# esp_car.net
KiCad netlist of a schematic drawn in EAGLE
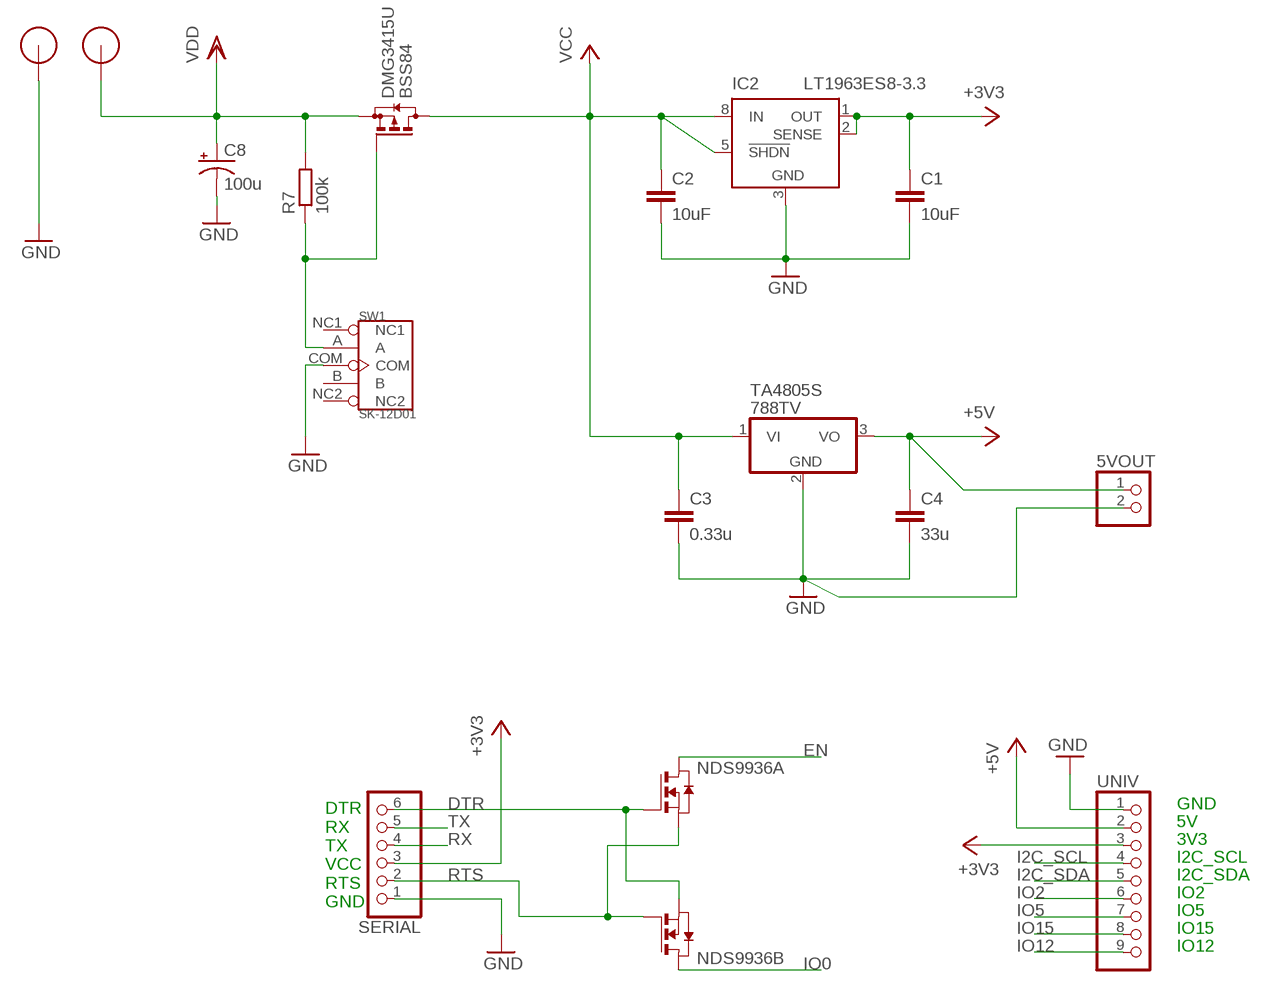
[diagram p0: schematic, sheet 1, part 1 of 2]
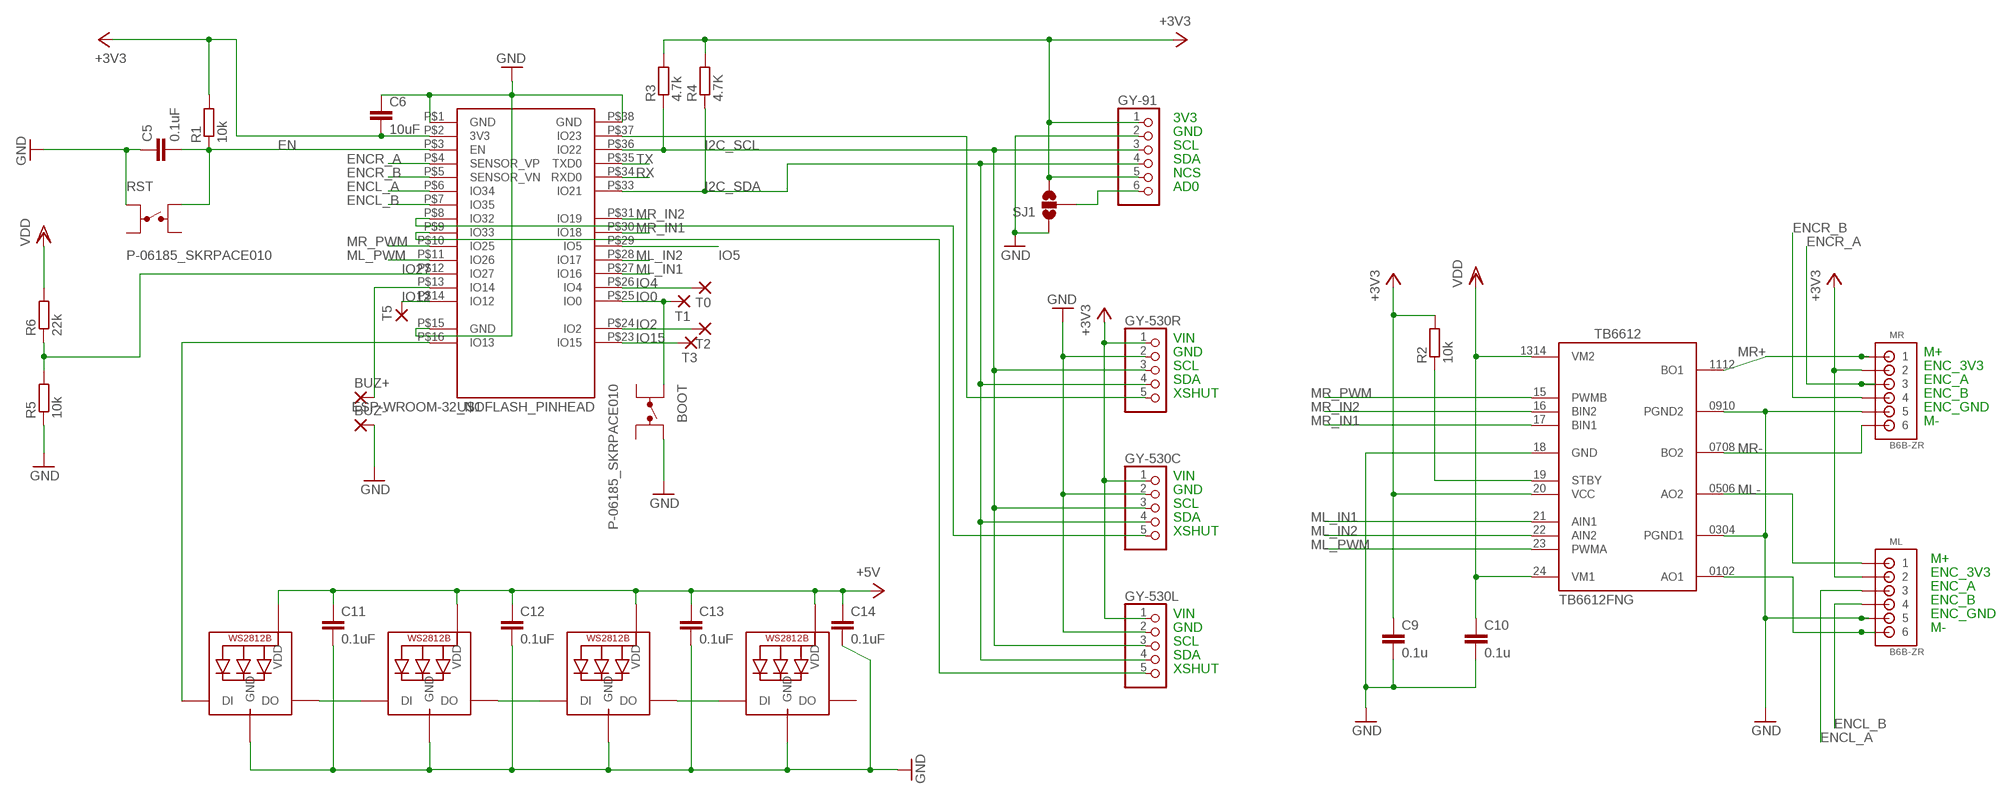
[diagram p1: schematic, sheet 1, part 2 of 2]

(export (version "E")
  (design (tool "Eeschema 10.0.6"))
  (components
    (comp (ref "5VOUT")
      (value "PINHD-1X2")
      (footprint "eagle-import:1X02")
      (libsource (lib "eagle-import") (part "PINHD-1X2"))
    )
    (comp (ref "BOOT")
      (value "P-06185_SKRPACE010")
      (footprint "eagle-import:SKRP")
      (libsource (lib "eagle-import") (part "P-06185_SKRPACE010"))
    )
    (comp (ref "BUZ+")
      (value "SMD2")
      (footprint "eagle-import:SMD1,27-2,54")
      (libsource (lib "eagle-import") (part "SMD2"))
    )
    (comp (ref "BUZ-")
      (value "SMD2")
      (footprint "eagle-import:SMD1,27-2,54")
      (libsource (lib "eagle-import") (part "SMD2"))
    )
    (comp (ref "C1")
      (value "10uF")
      (footprint "eagle-import:C1608")
      (libsource (lib "eagle-import") (part "C-EUC1608"))
    )
    (comp (ref "C2")
      (value "10uF")
      (footprint "eagle-import:C1608")
      (libsource (lib "eagle-import") (part "C-EUC1608"))
    )
    (comp (ref "C3")
      (value "0.33u")
      (footprint "eagle-import:C1608")
      (libsource (lib "eagle-import") (part "C-EUC1608"))
    )
    (comp (ref "C4")
      (value "33u")
      (footprint "eagle-import:C3225")
      (libsource (lib "eagle-import") (part "C-EUC3225"))
    )
    (comp (ref "C5")
      (value "0.1uF")
      (footprint "eagle-import:C1608")
      (libsource (lib "eagle-import") (part "C-EUC1608"))
    )
    (comp (ref "C6")
      (value "10uF")
      (footprint "eagle-import:C1608")
      (libsource (lib "eagle-import") (part "C-EUC1608"))
    )
    (comp (ref "C8")
      (value "100u")
      (footprint "eagle-import:E2,5-6")
      (libsource (lib "eagle-import") (part "CPOL-USE2.5-6"))
    )
    (comp (ref "C9")
      (value "0.1u")
      (footprint "eagle-import:C1608")
      (libsource (lib "eagle-import") (part "C-EUC1608"))
    )
    (comp (ref "C10")
      (value "0.1u")
      (footprint "eagle-import:C1608")
      (libsource (lib "eagle-import") (part "C-EUC1608"))
    )
    (comp (ref "C11")
      (value "0.1uF")
      (footprint "eagle-import:C1608")
      (libsource (lib "eagle-import") (part "C-EUC1608"))
    )
    (comp (ref "C12")
      (value "0.1uF")
      (footprint "eagle-import:C1608")
      (libsource (lib "eagle-import") (part "C-EUC1608"))
    )
    (comp (ref "C13")
      (value "0.1uF")
      (footprint "eagle-import:C1608")
      (libsource (lib "eagle-import") (part "C-EUC1608"))
    )
    (comp (ref "C14")
      (value "0.1uF")
      (footprint "eagle-import:C1608")
      (libsource (lib "eagle-import") (part "C-EUC1608"))
    )
    (comp (ref "DMG3415U")
      (value "BSS84")
      (footprint "eagle-import:SOT23")
      (libsource (lib "eagle-import") (part "BSS84"))
    )
    (comp (ref "GY-91")
      (value "PINHD-1X6")
      (footprint "eagle-import:1X06")
      (libsource (lib "eagle-import") (part "PINHD-1X6"))
    )
    (comp (ref "GY-530C")
      (value "PINHD-1X5")
      (footprint "eagle-import:1X05")
      (libsource (lib "eagle-import") (part "PINHD-1X5"))
    )
    (comp (ref "GY-530L")
      (value "PINHD-1X5")
      (footprint "eagle-import:1X05")
      (libsource (lib "eagle-import") (part "PINHD-1X5"))
    )
    (comp (ref "GY-530R")
      (value "PINHD-1X5")
      (footprint "eagle-import:1X05")
      (libsource (lib "eagle-import") (part "PINHD-1X5"))
    )
    (comp (ref "IC2")
      (value "LT1963ES8-3.3")
      (footprint "eagle-import:SOIC8")
      (libsource (lib "eagle-import") (part "LT1963ES8-3.3"))
    )
    (comp (ref "LED_FL")
      (value "WS2812B5050")
      (footprint "eagle-import:WS2812B")
      (libsource (lib "eagle-import") (part "WS2812B5050"))
    )
    (comp (ref "LED_FR")
      (value "WS2812B5050")
      (footprint "eagle-import:WS2812B")
      (libsource (lib "eagle-import") (part "WS2812B5050"))
    )
    (comp (ref "LED_RL")
      (value "WS2812B5050")
      (footprint "eagle-import:WS2812B")
      (libsource (lib "eagle-import") (part "WS2812B5050"))
    )
    (comp (ref "LED_RR")
      (value "WS2812B5050")
      (footprint "eagle-import:WS2812B")
      (libsource (lib "eagle-import") (part "WS2812B5050"))
    )
    (comp (ref "ML")
      (value "B6B-ZR")
      (footprint "eagle-import:B6B-ZR")
      (libsource (lib "eagle-import") (part "B6B-ZR"))
    )
    (comp (ref "MR")
      (value "B6B-ZR")
      (footprint "eagle-import:B6B-ZR")
      (libsource (lib "eagle-import") (part "B6B-ZR"))
    )
    (comp (ref "NDS9936")
      (value "NMOS2SO8")
      (footprint "eagle-import:SO8")
      (libsource (lib "eagle-import") (part "NMOS2SO8"))
    )
    (comp (ref "R1")
      (value "10k")
      (footprint "eagle-import:R0603")
      (libsource (lib "eagle-import") (part "R-EU_R0603"))
    )
    (comp (ref "R2")
      (value "10k")
      (footprint "eagle-import:R0603")
      (libsource (lib "eagle-import") (part "R-EU_R0603"))
    )
    (comp (ref "R3")
      (value "4.7k")
      (footprint "eagle-import:R0603")
      (libsource (lib "eagle-import") (part "R-EU_R0603"))
    )
    (comp (ref "R4")
      (value "4.7K")
      (footprint "eagle-import:R0603")
      (libsource (lib "eagle-import") (part "R-EU_R0603"))
    )
    (comp (ref "R5")
      (value "10k")
      (footprint "eagle-import:R0603")
      (libsource (lib "eagle-import") (part "R-EU_R0603"))
    )
    (comp (ref "R6")
      (value "22k")
      (footprint "eagle-import:R0603")
      (libsource (lib "eagle-import") (part "R-EU_R0603"))
    )
    (comp (ref "R7")
      (value "100k")
      (footprint "eagle-import:R0603")
      (libsource (lib "eagle-import") (part "R-EU_R0603"))
    )
    (comp (ref "RST")
      (value "P-06185_SKRPACE010")
      (footprint "eagle-import:SKRP")
      (libsource (lib "eagle-import") (part "P-06185_SKRPACE010"))
    )
    (comp (ref "SERIAL")
      (value "PINHD-1X6")
      (footprint "eagle-import:1X06")
      (libsource (lib "eagle-import") (part "PINHD-1X6"))
    )
    (comp (ref "SJ1")
      (value "SOLDERJUMPER_2WAYS")
      (footprint "eagle-import:SJ_3")
      (libsource (lib "eagle-import") (part "SOLDERJUMPER_2WAYS"))
    )
    (comp (ref "SW1")
      (value "SK-12D01")
      (footprint "eagle-import:SW5-2.0-8.8X4.4X4.7MM-90D")
      (libsource (lib "eagle-import") (part "DIP-TOGGLE-SWITCH-ON-ON(3+2P-8.8X4.6MM)"))
    )
    (comp (ref "T0")
      (value "SMD5")
      (footprint "eagle-import:SMD2,54-5,08")
      (libsource (lib "eagle-import") (part "SMD5"))
    )
    (comp (ref "T1")
      (value "SMD5")
      (footprint "eagle-import:SMD2,54-5,08")
      (libsource (lib "eagle-import") (part "SMD5"))
    )
    (comp (ref "T2")
      (value "SMD5")
      (footprint "eagle-import:SMD2,54-5,08")
      (libsource (lib "eagle-import") (part "SMD5"))
    )
    (comp (ref "T3")
      (value "SMD5")
      (footprint "eagle-import:SMD2,54-5,08")
      (libsource (lib "eagle-import") (part "SMD5"))
    )
    (comp (ref "T5")
      (value "SMD5")
      (footprint "eagle-import:SMD2,54-5,08")
      (libsource (lib "eagle-import") (part "SMD5"))
    )
    (comp (ref "TA4805S")
      (value "788TV")
      (footprint "eagle-import:TO220V")
      (libsource (lib "eagle-import") (part "78TV8"))
    )
    (comp (ref "TB6612")
      (value "TB6612_NEW")
      (footprint "eagle-import:SSOP24_TB6612")
      (libsource (lib "eagle-import") (part "TB6612_NEW"))
    )
    (comp (ref "U$1")
      (value "ESP-WROOM-32_NOFLASH_PINHEAD")
      (footprint "eagle-import:ESP-WROOM-32_NOFLASH_PINHEAD")
      (libsource (lib "eagle-import") (part "ESP-WROOM-32_NOFLASH_PINHEAD"))
    )
    (comp (ref "U$5")
      (value "2.0")
      (footprint "eagle-import:2.0")
      (libsource (lib "eagle-import") (part "2.0"))
    )
    (comp (ref "U$7")
      (value "2.0")
      (footprint "eagle-import:2.0")
      (libsource (lib "eagle-import") (part "2.0"))
    )
    (comp (ref "UNIV")
      (value "PINHD-1X9")
      (footprint "eagle-import:1X09-BIG")
      (libsource (lib "eagle-import") (part "PINHD-1X9"))
    )
  )
  (nets
    (net (code "1") (name "+3V3") (class "Default")
      (node (ref "C1") (pin "1") (pinfunction "1_1") (pintype "passive"))
      (node (ref "C6") (pin "2") (pinfunction "2_2") (pintype "passive"))
      (node (ref "C9") (pin "1") (pinfunction "1_1") (pintype "passive"))
      (node (ref "GY-530C") (pin "1") (pinfunction "1_1") (pintype "passive"))
      (node (ref "GY-530L") (pin "1") (pinfunction "1_1") (pintype "passive"))
      (node (ref "GY-530R") (pin "1") (pinfunction "1_1") (pintype "passive"))
      (node (ref "GY-91") (pin "1") (pinfunction "1_1") (pintype "passive"))
      (node (ref "GY-91") (pin "5") (pinfunction "5_5") (pintype "passive"))
      (node (ref "IC2") (pin "1") (pinfunction "OUT_1") (pintype "output"))
      (node (ref "IC2") (pin "2") (pinfunction "SENSE_2") (pintype "input"))
      (node (ref "ML") (pin "2") (pinfunction "2_2") (pintype "bidirectional"))
      (node (ref "MR") (pin "2") (pinfunction "2_2") (pintype "bidirectional"))
      (node (ref "R1") (pin "2") (pinfunction "2_2") (pintype "passive"))
      (node (ref "R2") (pin "2") (pinfunction "2_2") (pintype "passive"))
      (node (ref "R3") (pin "2") (pinfunction "2_2") (pintype "passive"))
      (node (ref "R4") (pin "2") (pinfunction "2_2") (pintype "passive"))
      (node (ref "SERIAL") (pin "3") (pinfunction "3_3") (pintype "passive"))
      (node (ref "SJ1") (pin "3") (pinfunction "3_3") (pintype "passive"))
      (node (ref "TB6612") (pin "20") (pinfunction "VCC_20") (pintype "power_in"))
      (node (ref "U$1") (pin "P$2") (pinfunction "3V3_P$2") (pintype "power_in"))
      (node (ref "UNIV") (pin "3") (pinfunction "3_3") (pintype "passive"))
    )
    (net (code "2") (name "+5V") (class "Default")
      (node (ref "5VOUT") (pin "1") (pinfunction "1_1") (pintype "passive"))
      (node (ref "C11") (pin "1") (pinfunction "1_1") (pintype "passive"))
      (node (ref "C12") (pin "1") (pinfunction "1_1") (pintype "passive"))
      (node (ref "C13") (pin "1") (pinfunction "1_1") (pintype "passive"))
      (node (ref "C14") (pin "1") (pinfunction "1_1") (pintype "passive"))
      (node (ref "C4") (pin "1") (pinfunction "1_1") (pintype "passive"))
      (node (ref "LED_FL") (pin "1-VDD") (pinfunction "VDD_1-VDD") (pintype "power_in"))
      (node (ref "LED_FR") (pin "1-VDD") (pinfunction "VDD_1-VDD") (pintype "power_in"))
      (node (ref "LED_RL") (pin "1-VDD") (pinfunction "VDD_1-VDD") (pintype "power_in"))
      (node (ref "LED_RR") (pin "1-VDD") (pinfunction "VDD_1-VDD") (pintype "power_in"))
      (node (ref "TA4805S") (pin "3") (pinfunction "VO_3") (pintype "passive"))
      (node (ref "UNIV") (pin "2") (pinfunction "2_2") (pintype "passive"))
    )
    (net (code "3") (name "/DTR") (class "Default")
      (node (ref "NDS9936") (pin "2") (pinfunction "G_2") (pintype "passive"))
      (node (ref "NDS9936") (pin "3") (pinfunction "S_3") (pintype "passive"))
      (node (ref "SERIAL") (pin "6") (pinfunction "6_6") (pintype "passive"))
    )
    (net (code "4") (name "/EN") (class "Default")
      (node (ref "C5") (pin "2") (pinfunction "2_2") (pintype "passive"))
      (node (ref "NDS9936") (pin "7") (pinfunction "D_7") (pintype "passive"))
      (node (ref "NDS9936") (pin "8") (pinfunction "D_8") (pintype "passive"))
      (node (ref "R1") (pin "1") (pinfunction "1_1") (pintype "passive"))
      (node (ref "RST") (pin "2A") (pinfunction "P$2A_2A") (pintype "bidirectional"))
      (node (ref "U$1") (pin "P$3") (pinfunction "EN_P$3") (pintype "input"))
    )
    (net (code "5") (name "/ENCL_A") (class "Default")
      (node (ref "ML") (pin "3") (pinfunction "3_3") (pintype "bidirectional"))
      (node (ref "U$1") (pin "P$6") (pinfunction "IO34_P$6") (pintype "bidirectional"))
    )
    (net (code "6") (name "/ENCL_B") (class "Default")
      (node (ref "ML") (pin "4") (pinfunction "4_4") (pintype "bidirectional"))
      (node (ref "U$1") (pin "P$7") (pinfunction "IO35_P$7") (pintype "bidirectional"))
    )
    (net (code "7") (name "/ENCR_A") (class "Default")
      (node (ref "MR") (pin "3") (pinfunction "3_3") (pintype "bidirectional"))
      (node (ref "U$1") (pin "P$4") (pinfunction "SENSOR_VP_P$4") (pintype "bidirectional"))
    )
    (net (code "8") (name "/ENCR_B") (class "Default")
      (node (ref "MR") (pin "4") (pinfunction "4_4") (pintype "bidirectional"))
      (node (ref "U$1") (pin "P$5") (pinfunction "SENSOR_VN_P$5") (pintype "bidirectional"))
    )
    (net (code "9") (name "/I2C_SCL") (class "Default")
      (node (ref "GY-530C") (pin "3") (pinfunction "3_3") (pintype "passive"))
      (node (ref "GY-530L") (pin "3") (pinfunction "3_3") (pintype "passive"))
      (node (ref "GY-530R") (pin "3") (pinfunction "3_3") (pintype "passive"))
      (node (ref "GY-91") (pin "3") (pinfunction "3_3") (pintype "passive"))
      (node (ref "R3") (pin "1") (pinfunction "1_1") (pintype "passive"))
      (node (ref "U$1") (pin "P$36") (pinfunction "IO22_P$36") (pintype "bidirectional"))
      (node (ref "UNIV") (pin "4") (pinfunction "4_4") (pintype "passive"))
    )
    (net (code "10") (name "/I2C_SDA") (class "Default")
      (node (ref "GY-530C") (pin "4") (pinfunction "4_4") (pintype "passive"))
      (node (ref "GY-530L") (pin "4") (pinfunction "4_4") (pintype "passive"))
      (node (ref "GY-530R") (pin "4") (pinfunction "4_4") (pintype "passive"))
      (node (ref "GY-91") (pin "4") (pinfunction "4_4") (pintype "passive"))
      (node (ref "R4") (pin "1") (pinfunction "1_1") (pintype "passive"))
      (node (ref "U$1") (pin "P$33") (pinfunction "IO21_P$33") (pintype "bidirectional"))
      (node (ref "UNIV") (pin "5") (pinfunction "5_5") (pintype "passive"))
    )
    (net (code "11") (name "/IO0") (class "Default")
      (node (ref "BOOT") (pin "1A") (pinfunction "P$1A_1A") (pintype "bidirectional"))
      (node (ref "NDS9936") (pin "5") (pinfunction "D_5") (pintype "passive"))
      (node (ref "NDS9936") (pin "6") (pinfunction "D_6") (pintype "passive"))
      (node (ref "T1") (pin "1") (pinfunction "P_1") (pintype "passive"))
      (node (ref "U$1") (pin "P$25") (pinfunction "IO0_P$25") (pintype "bidirectional"))
    )
    (net (code "12") (name "/IO2") (class "Default")
      (node (ref "T2") (pin "1") (pinfunction "P_1") (pintype "passive"))
      (node (ref "U$1") (pin "P$24") (pinfunction "IO2_P$24") (pintype "bidirectional"))
      (node (ref "UNIV") (pin "6") (pinfunction "6_6") (pintype "passive"))
    )
    (net (code "13") (name "/IO4") (class "Default")
      (node (ref "T0") (pin "1") (pinfunction "P_1") (pintype "passive"))
      (node (ref "U$1") (pin "P$26") (pinfunction "IO4_P$26") (pintype "bidirectional"))
    )
    (net (code "14") (name "/IO5") (class "Default")
      (node (ref "U$1") (pin "P$29") (pinfunction "IO5_P$29") (pintype "bidirectional"))
      (node (ref "UNIV") (pin "7") (pinfunction "7_7") (pintype "passive"))
    )
    (net (code "15") (name "/IO12") (class "Default")
      (node (ref "T5") (pin "1") (pinfunction "P_1") (pintype "passive"))
      (node (ref "U$1") (pin "P$14") (pinfunction "IO12_P$14") (pintype "bidirectional"))
      (node (ref "UNIV") (pin "9") (pinfunction "9_9") (pintype "passive"))
    )
    (net (code "16") (name "/IO15") (class "Default")
      (node (ref "T3") (pin "1") (pinfunction "P_1") (pintype "passive"))
      (node (ref "U$1") (pin "P$23") (pinfunction "IO15_P$23") (pintype "bidirectional"))
      (node (ref "UNIV") (pin "8") (pinfunction "8_8") (pintype "passive"))
    )
    (net (code "17") (name "/IO27") (class "Default")
      (node (ref "R5") (pin "2") (pinfunction "2_2") (pintype "passive"))
      (node (ref "R6") (pin "1") (pinfunction "1_1") (pintype "passive"))
      (node (ref "U$1") (pin "P$12") (pinfunction "IO27_P$12") (pintype "bidirectional"))
    )
    (net (code "18") (name "/ML-") (class "Default")
      (node (ref "ML") (pin "6") (pinfunction "6_6") (pintype "bidirectional"))
      (node (ref "TB6612") (pin "0102") (pinfunction "AO1_0102") (pintype "output"))
    )
    (net (code "19") (name "/ML_IN1") (class "Default")
      (node (ref "TB6612") (pin "21") (pinfunction "AIN1_21") (pintype "input"))
      (node (ref "U$1") (pin "P$27") (pinfunction "IO16_P$27") (pintype "bidirectional"))
    )
    (net (code "20") (name "/ML_IN2") (class "Default")
      (node (ref "TB6612") (pin "22") (pinfunction "AIN2_22") (pintype "input"))
      (node (ref "U$1") (pin "P$28") (pinfunction "IO17_P$28") (pintype "bidirectional"))
    )
    (net (code "21") (name "/ML_PWM") (class "Default")
      (node (ref "TB6612") (pin "23") (pinfunction "PWMA_23") (pintype "input"))
      (node (ref "U$1") (pin "P$11") (pinfunction "IO26_P$11") (pintype "bidirectional"))
    )
    (net (code "22") (name "/MR+") (class "Default")
      (node (ref "MR") (pin "1") (pinfunction "1_1") (pintype "bidirectional"))
      (node (ref "TB6612") (pin "1112") (pinfunction "BO1_1112") (pintype "output"))
    )
    (net (code "23") (name "/MR-") (class "Default")
      (node (ref "MR") (pin "6") (pinfunction "6_6") (pintype "bidirectional"))
      (node (ref "TB6612") (pin "0708") (pinfunction "BO2_0708") (pintype "output"))
    )
    (net (code "24") (name "/MR_IN1") (class "Default")
      (node (ref "TB6612") (pin "17") (pinfunction "BIN1_17") (pintype "input"))
      (node (ref "U$1") (pin "P$30") (pinfunction "IO18_P$30") (pintype "bidirectional"))
    )
    (net (code "25") (name "/MR_IN2") (class "Default")
      (node (ref "TB6612") (pin "16") (pinfunction "BIN2_16") (pintype "input"))
      (node (ref "U$1") (pin "P$31") (pinfunction "IO19_P$31") (pintype "bidirectional"))
    )
    (net (code "26") (name "/MR_PWM") (class "Default")
      (node (ref "TB6612") (pin "15") (pinfunction "PWMB_15") (pintype "input"))
      (node (ref "U$1") (pin "P$10") (pinfunction "IO25_P$10") (pintype "bidirectional"))
    )
    (net (code "27") (name "/RTS") (class "Default")
      (node (ref "NDS9936") (pin "1") (pinfunction "S_1") (pintype "passive"))
      (node (ref "NDS9936") (pin "4") (pinfunction "G_4") (pintype "passive"))
      (node (ref "SERIAL") (pin "2") (pinfunction "2_2") (pintype "passive"))
    )
    (net (code "28") (name "/RX") (class "Default")
      (node (ref "SERIAL") (pin "4") (pinfunction "4_4") (pintype "passive"))
      (node (ref "U$1") (pin "P$34") (pinfunction "RXD0_P$34") (pintype "bidirectional"))
    )
    (net (code "29") (name "/TX") (class "Default")
      (node (ref "SERIAL") (pin "5") (pinfunction "5_5") (pintype "passive"))
      (node (ref "U$1") (pin "P$35") (pinfunction "TXD0_P$35") (pintype "bidirectional"))
    )
    (net (code "30") (name "GND") (class "Default")
      (node (ref "5VOUT") (pin "2") (pinfunction "2_2") (pintype "passive"))
      (node (ref "BOOT") (pin "2A") (pinfunction "P$2A_2A") (pintype "bidirectional"))
      (node (ref "BUZ-") (pin "1") (pinfunction "P_1") (pintype "passive"))
      (node (ref "C1") (pin "2") (pinfunction "2_2") (pintype "passive"))
      (node (ref "C10") (pin "2") (pinfunction "2_2") (pintype "passive"))
      (node (ref "C11") (pin "2") (pinfunction "2_2") (pintype "passive"))
      (node (ref "C12") (pin "2") (pinfunction "2_2") (pintype "passive"))
      (node (ref "C13") (pin "2") (pinfunction "2_2") (pintype "passive"))
      (node (ref "C14") (pin "2") (pinfunction "2_2") (pintype "passive"))
      (node (ref "C2") (pin "2") (pinfunction "2_2") (pintype "passive"))
      (node (ref "C3") (pin "2") (pinfunction "2_2") (pintype "passive"))
      (node (ref "C4") (pin "2") (pinfunction "2_2") (pintype "passive"))
      (node (ref "C5") (pin "1") (pinfunction "1_1") (pintype "passive"))
      (node (ref "C6") (pin "1") (pinfunction "1_1") (pintype "passive"))
      (node (ref "C8") (pin "-") (pinfunction "-_-") (pintype "passive"))
      (node (ref "C9") (pin "2") (pinfunction "2_2") (pintype "passive"))
      (node (ref "GY-530C") (pin "2") (pinfunction "2_2") (pintype "passive"))
      (node (ref "GY-530L") (pin "2") (pinfunction "2_2") (pintype "passive"))
      (node (ref "GY-530R") (pin "2") (pinfunction "2_2") (pintype "passive"))
      (node (ref "GY-91") (pin "2") (pinfunction "2_2") (pintype "passive"))
      (node (ref "IC2") (pin "3") (pinfunction "GND_3") (pintype "power_in"))
      (node (ref "LED_FL") (pin "3-GND") (pinfunction "GND_3-GND") (pintype "power_in"))
      (node (ref "LED_FR") (pin "3-GND") (pinfunction "GND_3-GND") (pintype "power_in"))
      (node (ref "LED_RL") (pin "3-GND") (pinfunction "GND_3-GND") (pintype "power_in"))
      (node (ref "LED_RR") (pin "3-GND") (pinfunction "GND_3-GND") (pintype "power_in"))
      (node (ref "ML") (pin "5") (pinfunction "5_5") (pintype "bidirectional"))
      (node (ref "MR") (pin "5") (pinfunction "5_5") (pintype "bidirectional"))
      (node (ref "R5") (pin "1") (pinfunction "1_1") (pintype "passive"))
      (node (ref "RST") (pin "1A") (pinfunction "P$1A_1A") (pintype "bidirectional"))
      (node (ref "SERIAL") (pin "1") (pinfunction "1_1") (pintype "passive"))
      (node (ref "SJ1") (pin "1") (pinfunction "1_1") (pintype "passive"))
      (node (ref "SW1") (pin "COM") (pinfunction "COM_COM") (pintype "bidirectional"))
      (node (ref "TA4805S") (pin "2") (pinfunction "GND_2") (pintype "passive"))
      (node (ref "TB6612") (pin "0304") (pinfunction "PGND1_0304") (pintype "power_in"))
      (node (ref "TB6612") (pin "0910") (pinfunction "PGND2_0910") (pintype "power_in"))
      (node (ref "TB6612") (pin "18") (pinfunction "GND_18") (pintype "power_in"))
      (node (ref "U$1") (pin "P$1") (pinfunction "GND_P$1") (pintype "power_in"))
      (node (ref "U$1") (pin "P$15") (pinfunction "GND_P$15") (pintype "power_in"))
      (node (ref "U$1") (pin "P$38") (pinfunction "GND_P$38") (pintype "power_in"))
      (node (ref "U$5") (pin "P$1") (pinfunction "P$1_P$1") (pintype "bidirectional"))
      (node (ref "UNIV") (pin "1") (pinfunction "1_1") (pintype "passive"))
    )
    (net (code "31") (name "Net-(BUZ+-P)") (class "Default")
      (node (ref "BUZ+") (pin "1") (pinfunction "P_1") (pintype "passive"))
      (node (ref "U$1") (pin "P$13") (pinfunction "IO14_P$13") (pintype "bidirectional"))
    )
    (net (code "32") (name "Net-(DMG3415U-G)") (class "Default")
      (node (ref "DMG3415U") (pin "1") (pinfunction "G_1") (pintype "passive"))
      (node (ref "R7") (pin "1") (pinfunction "1_1") (pintype "passive"))
      (node (ref "SW1") (pin "A") (pinfunction "A_A") (pintype "bidirectional"))
    )
    (net (code "33") (name "Net-(GY-91-Pad6)") (class "Default")
      (node (ref "GY-91") (pin "6") (pinfunction "6_6") (pintype "passive"))
      (node (ref "SJ1") (pin "2") (pinfunction "2_2") (pintype "passive"))
    )
    (net (code "34") (name "Net-(LED_FL-DI)") (class "Default")
      (node (ref "LED_FL") (pin "4-DIN") (pinfunction "DI_4-DIN") (pintype "input"))
      (node (ref "U$1") (pin "P$16") (pinfunction "IO13_P$16") (pintype "bidirectional"))
    )
    (net (code "35") (name "Net-(LED_FL-DO)") (class "Default")
      (node (ref "LED_FL") (pin "2-DOUT") (pinfunction "DO_2-DOUT") (pintype "output"))
      (node (ref "LED_RL") (pin "4-DIN") (pinfunction "DI_4-DIN") (pintype "input"))
    )
    (net (code "36") (name "Net-(LED_FR-DI)") (class "Default")
      (node (ref "LED_FR") (pin "4-DIN") (pinfunction "DI_4-DIN") (pintype "input"))
      (node (ref "LED_RR") (pin "2-DOUT") (pinfunction "DO_2-DOUT") (pintype "output"))
    )
    (net (code "37") (name "Net-(LED_RL-DO)") (class "Default")
      (node (ref "LED_RL") (pin "2-DOUT") (pinfunction "DO_2-DOUT") (pintype "output"))
      (node (ref "LED_RR") (pin "4-DIN") (pinfunction "DI_4-DIN") (pintype "input"))
    )
    (net (code "38") (name "Net-(TB6612-AO2)") (class "Default")
      (node (ref "ML") (pin "1") (pinfunction "1_1") (pintype "bidirectional"))
      (node (ref "TB6612") (pin "0506") (pinfunction "AO2_0506") (pintype "output"))
    )
    (net (code "39") (name "Net-(TB6612-STBY)") (class "Default")
      (node (ref "R2") (pin "1") (pinfunction "1_1") (pintype "passive"))
      (node (ref "TB6612") (pin "19") (pinfunction "STBY_19") (pintype "input"))
    )
    (net (code "40") (name "Net-(U$1-IO23)") (class "Default")
      (node (ref "GY-530R") (pin "5") (pinfunction "5_5") (pintype "passive"))
      (node (ref "U$1") (pin "P$37") (pinfunction "IO23_P$37") (pintype "bidirectional"))
    )
    (net (code "41") (name "Net-(U$1-IO32)") (class "Default")
      (node (ref "GY-530C") (pin "5") (pinfunction "5_5") (pintype "passive"))
      (node (ref "U$1") (pin "P$8") (pinfunction "IO32_P$8") (pintype "bidirectional"))
    )
    (net (code "42") (name "Net-(U$1-IO33)") (class "Default")
      (node (ref "GY-530L") (pin "5") (pinfunction "5_5") (pintype "passive"))
      (node (ref "U$1") (pin "P$9") (pinfunction "IO33_P$9") (pintype "bidirectional"))
    )
    (net (code "43") (name "VCC") (class "Default")
      (node (ref "C2") (pin "1") (pinfunction "1_1") (pintype "passive"))
      (node (ref "C3") (pin "1") (pinfunction "1_1") (pintype "passive"))
      (node (ref "DMG3415U") (pin "3") (pinfunction "D_3") (pintype "passive"))
      (node (ref "IC2") (pin "5") (pinfunction "~{SHDN}_5") (pintype "input"))
      (node (ref "IC2") (pin "8") (pinfunction "IN_8") (pintype "input"))
      (node (ref "TA4805S") (pin "1") (pinfunction "VI_1") (pintype "input"))
    )
    (net (code "44") (name "VDD") (class "Default")
      (node (ref "C10") (pin "1") (pinfunction "1_1") (pintype "passive"))
      (node (ref "C8") (pin "+") (pinfunction "+_+") (pintype "passive"))
      (node (ref "DMG3415U") (pin "2") (pinfunction "S_2") (pintype "passive"))
      (node (ref "R6") (pin "2") (pinfunction "2_2") (pintype "passive"))
      (node (ref "R7") (pin "2") (pinfunction "2_2") (pintype "passive"))
      (node (ref "TB6612") (pin "1314") (pinfunction "VM2_1314") (pintype "power_in"))
      (node (ref "TB6612") (pin "24") (pinfunction "VM1_24") (pintype "power_in"))
      (node (ref "U$7") (pin "P$1") (pinfunction "P$1_P$1") (pintype "bidirectional"))
    )
    (net (code "45") (name "unconnected-(BOOT-P$1B-Pad1B)") (class "Default")
      (node (ref "BOOT") (pin "1B") (pinfunction "P$1B_1B") (pintype "bidirectional"))
    )
    (net (code "46") (name "unconnected-(BOOT-P$2B-Pad2B)") (class "Default")
      (node (ref "BOOT") (pin "2B") (pinfunction "P$2B_2B") (pintype "bidirectional"))
    )
    (net (code "47") (name "unconnected-(LED_FR-DO-Pad2-DOUT)") (class "Default")
      (node (ref "LED_FR") (pin "2-DOUT") (pinfunction "DO_2-DOUT") (pintype "output"))
    )
    (net (code "48") (name "unconnected-(RST-P$1B-Pad1B)") (class "Default")
      (node (ref "RST") (pin "1B") (pinfunction "P$1B_1B") (pintype "bidirectional"))
    )
    (net (code "49") (name "unconnected-(RST-P$2B-Pad2B)") (class "Default")
      (node (ref "RST") (pin "2B") (pinfunction "P$2B_2B") (pintype "bidirectional"))
    )
    (net (code "50") (name "unconnected-(SW1-PadB)") (class "Default")
      (node (ref "SW1") (pin "B") (pinfunction "B_B") (pintype "bidirectional"))
    )
    (net (code "51") (name "unconnected-(SW1-PadNC1)") (class "Default")
      (node (ref "SW1") (pin "NC1") (pinfunction "NC1_NC1") (pintype "bidirectional"))
    )
    (net (code "52") (name "unconnected-(SW1-PadNC2)") (class "Default")
      (node (ref "SW1") (pin "NC2") (pinfunction "NC2_NC2") (pintype "bidirectional"))
    )
  )
)
